# main-stm-02_2.net
KiCad netlist of a schematic drawn in EAGLE
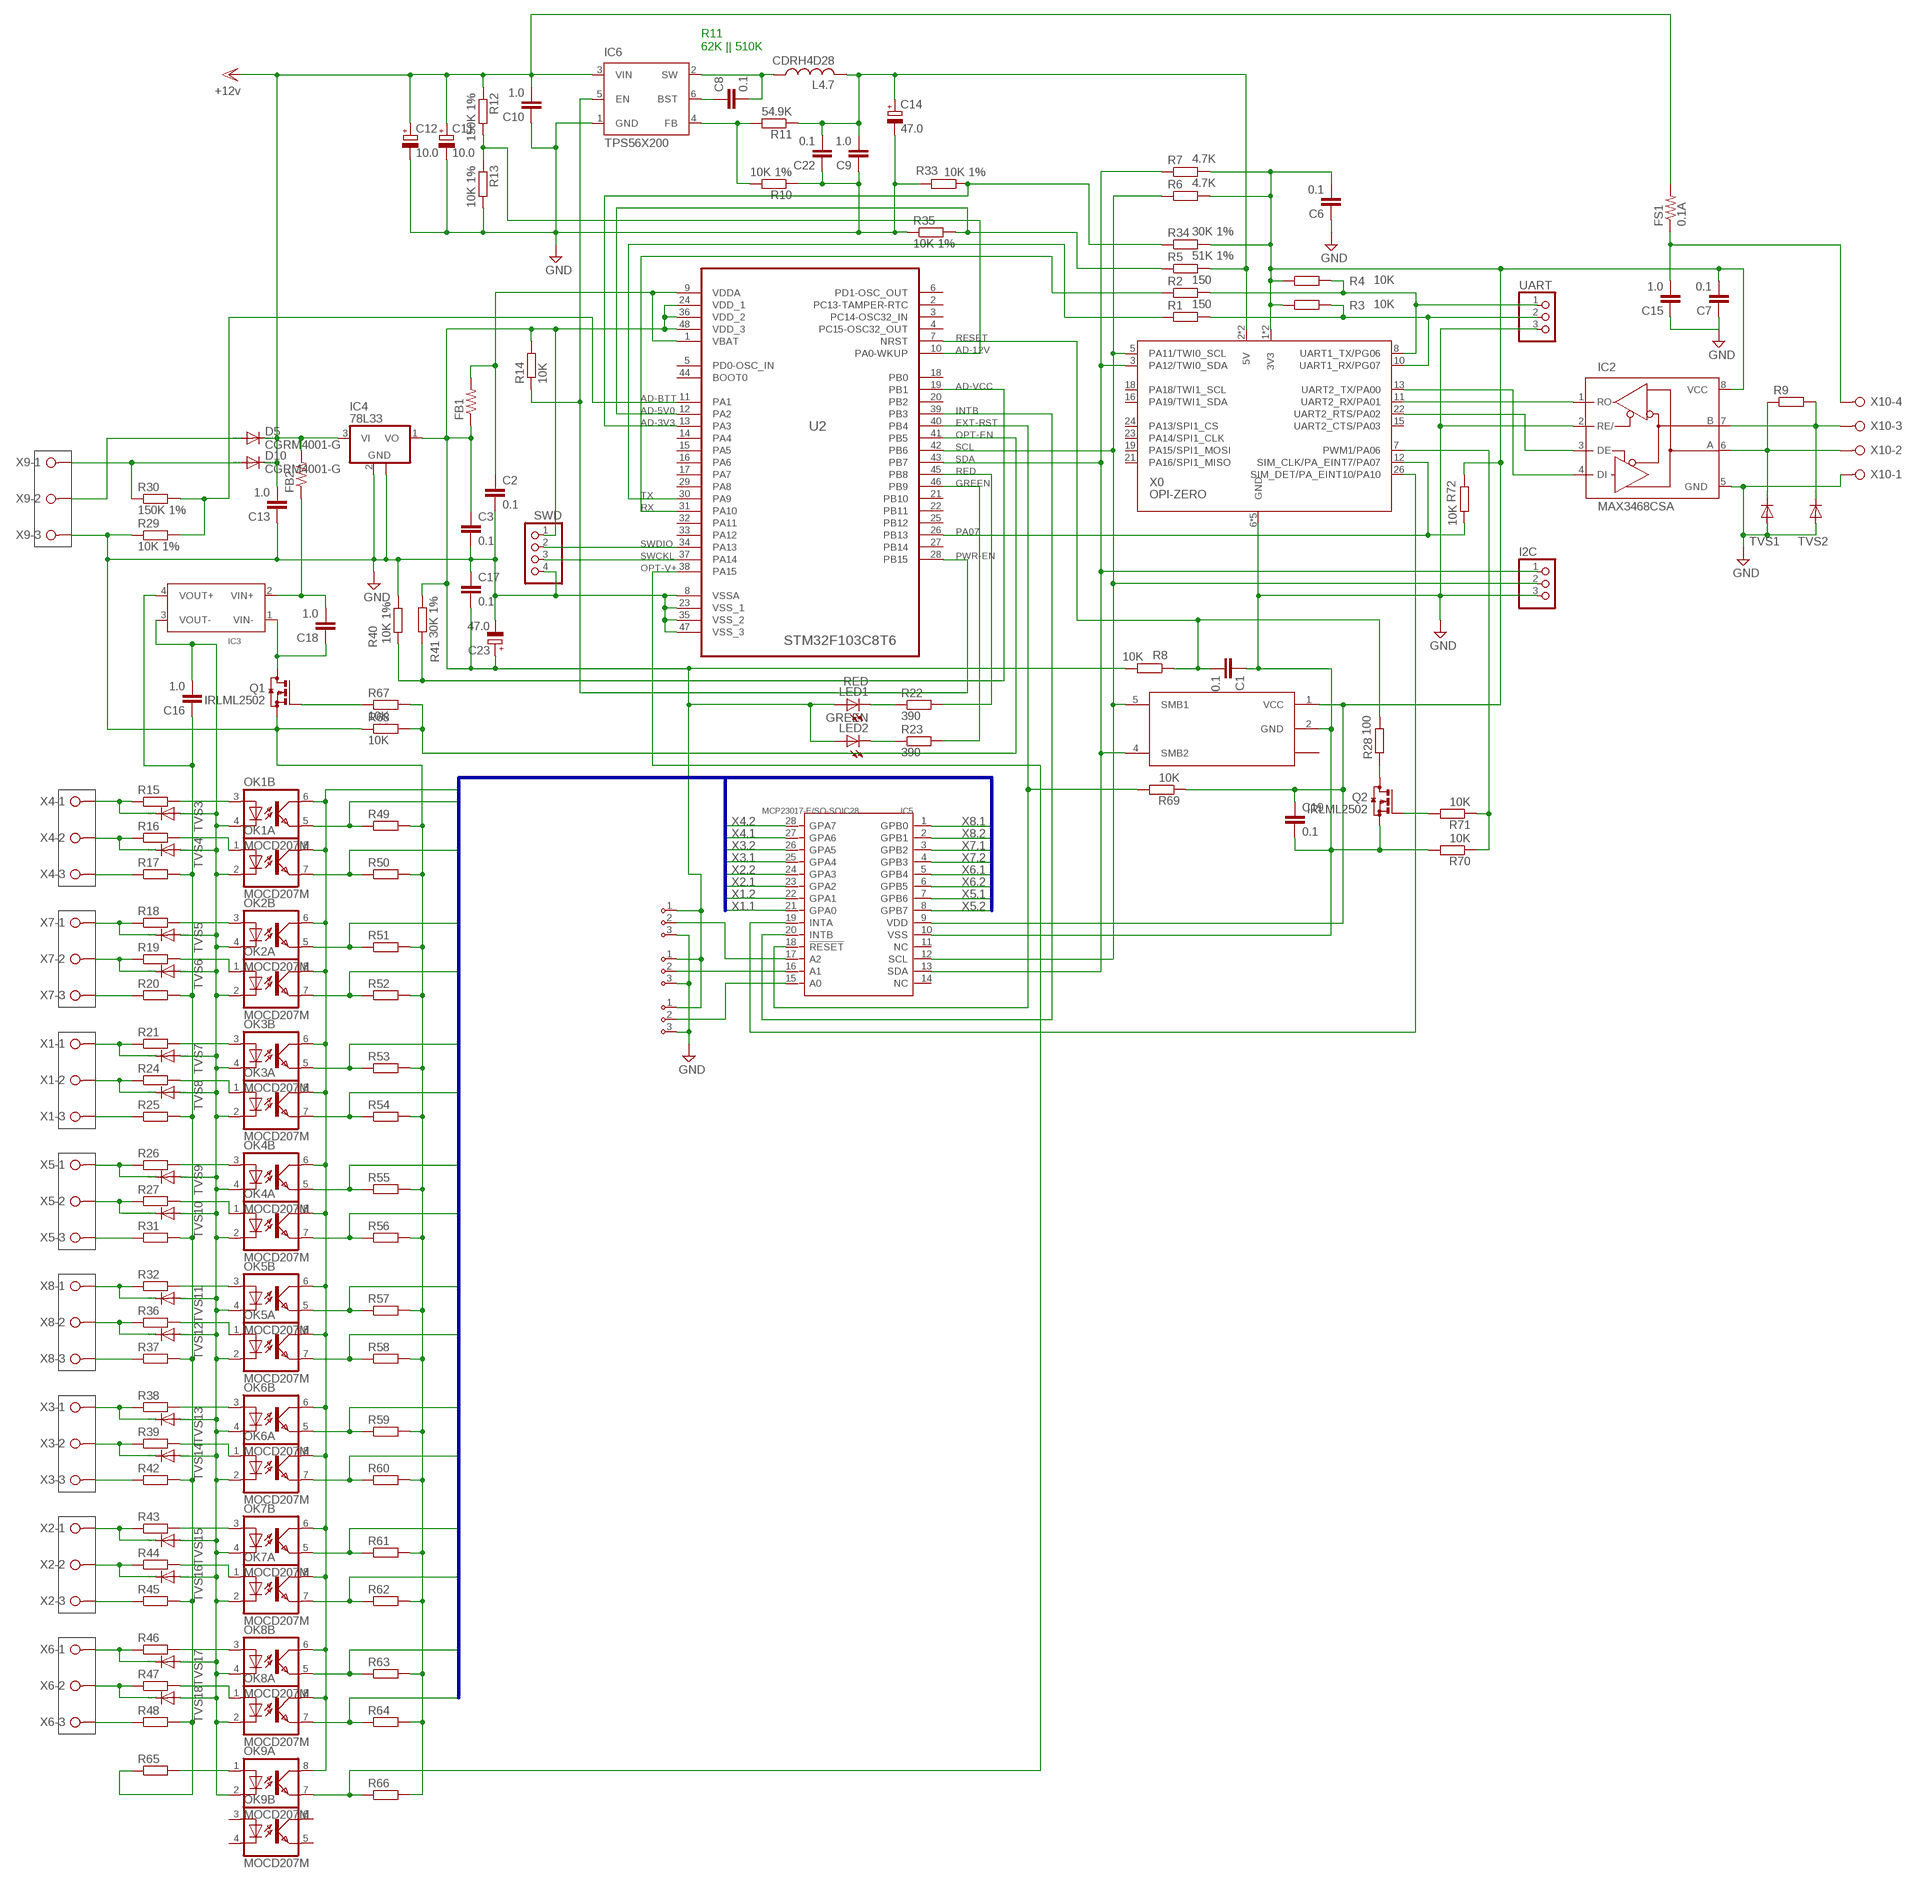
[diagram p0: schematic, sheet 1]

(export (version "E")
  (design (tool "Eeschema 10.0.6"))
  (components
    (comp (ref "A0")
      (value "ADDR3PIN0603")
      (footprint "eagle-import:0603-3PIN")
      (libsource (lib "eagle-import") (part "ADDR3PIN0603"))
    )
    (comp (ref "A1")
      (value "ADDR3PIN0603")
      (footprint "eagle-import:0603-3PIN")
      (libsource (lib "eagle-import") (part "ADDR3PIN0603"))
    )
    (comp (ref "A2")
      (value "ADDR3PIN0603")
      (footprint "eagle-import:0603-3PIN")
      (libsource (lib "eagle-import") (part "ADDR3PIN0603"))
    )
    (comp (ref "C1")
      (value "0.1")
      (footprint "eagle-import:C0603")
      (libsource (lib "eagle-import") (part "C-EUC0603"))
    )
    (comp (ref "C2")
      (value "0.1")
      (footprint "eagle-import:C0603")
      (libsource (lib "eagle-import") (part "C-EUC0603"))
    )
    (comp (ref "C3")
      (value "0.1")
      (footprint "eagle-import:C0603")
      (libsource (lib "eagle-import") (part "C-EUC0603"))
    )
    (comp (ref "C6")
      (value "0.1")
      (footprint "eagle-import:C0805")
      (libsource (lib "eagle-import") (part "C-EUC0805"))
    )
    (comp (ref "C7")
      (value "0.1")
      (footprint "eagle-import:C0805")
      (libsource (lib "eagle-import") (part "C-EUC0805"))
    )
    (comp (ref "C8")
      (value "0.1")
      (footprint "eagle-import:C0805")
      (libsource (lib "eagle-import") (part "C-EUC0805"))
    )
    (comp (ref "C9")
      (value "1.0")
      (footprint "eagle-import:C0805")
      (libsource (lib "eagle-import") (part "C-EUC0805"))
    )
    (comp (ref "C10")
      (value "1.0")
      (footprint "eagle-import:C1206")
      (libsource (lib "eagle-import") (part "C-EUC1206"))
    )
    (comp (ref "C11")
      (value "10.0")
      (footprint "eagle-import:C_6032-28R")
      (libsource (lib "eagle-import") (part "CPOL-EUC/6032-28R"))
    )
    (comp (ref "C12")
      (value "10.0")
      (footprint "eagle-import:C_6032-28R")
      (libsource (lib "eagle-import") (part "CPOL-EUC/6032-28R"))
    )
    (comp (ref "C13")
      (value "1.0")
      (footprint "eagle-import:C1206")
      (libsource (lib "eagle-import") (part "C-EUC1206"))
    )
    (comp (ref "C14")
      (value "47.0")
      (footprint "eagle-import:B_3528-21R")
      (libsource (lib "eagle-import") (part "CPOL-EUB/3528-21R"))
    )
    (comp (ref "C15")
      (value "1.0")
      (footprint "eagle-import:C1206")
      (libsource (lib "eagle-import") (part "C-EUC1206"))
    )
    (comp (ref "C16")
      (value "1.0")
      (footprint "eagle-import:C1206")
      (libsource (lib "eagle-import") (part "C-EUC1206"))
    )
    (comp (ref "C17")
      (value "0.1")
      (footprint "eagle-import:C0603")
      (libsource (lib "eagle-import") (part "C-EUC0603"))
    )
    (comp (ref "C18")
      (value "1.0")
      (footprint "eagle-import:C1206")
      (libsource (lib "eagle-import") (part "C-EUC1206"))
    )
    (comp (ref "C19")
      (value "0.1")
      (footprint "eagle-import:C0603")
      (libsource (lib "eagle-import") (part "C-EUC0603"))
    )
    (comp (ref "C22")
      (value "0.1")
      (footprint "eagle-import:C0805")
      (libsource (lib "eagle-import") (part "C-EUC0805"))
    )
    (comp (ref "C23")
      (value "47.0")
      (footprint "eagle-import:B_3528-21R")
      (libsource (lib "eagle-import") (part "CPOL-EUB/3528-21R"))
    )
    (comp (ref "D5")
      (value "CGRM4001-G")
      (footprint "eagle-import:SOD-123_MINI-SMA")
      (libsource (lib "eagle-import") (part "CGRM400-G1"))
    )
    (comp (ref "D10")
      (value "CGRM4001-G")
      (footprint "eagle-import:SOD-123_MINI-SMA")
      (libsource (lib "eagle-import") (part "CGRM400-G1"))
    )
    (comp (ref "FB1")
      (value "R-US_R0805")
      (footprint "eagle-import:R0805")
      (libsource (lib "eagle-import") (part "R-US_R0805"))
    )
    (comp (ref "FB2")
      (value "R-US_R1206")
      (footprint "eagle-import:R1206")
      (libsource (lib "eagle-import") (part "R-US_R1206"))
    )
    (comp (ref "FS1")
      (value "0.1A")
      (footprint "eagle-import:R1210")
      (libsource (lib "eagle-import") (part "R-US_R1210"))
    )
    (comp (ref "I2C")
      (value "PINHD-1X3")
      (footprint "eagle-import:1X03")
      (libsource (lib "eagle-import") (part "PINHD-1X3"))
    )
    (comp (ref "IC2")
      (value "MAX3468CSA")
      (footprint "eagle-import:SO08")
      (fields (field (name "MPN") "MAX3468CSA+"))
      (libsource (lib "eagle-import") (part "MAX34SA68C"))
    )
    (comp (ref "IC3")
      (value "DC-DC-CONV-4PIN-ISOLATINGMURATA-NME-05-12-SERIES")
      (footprint "eagle-import:DC-DC-MURATA-NME-05-12-SERIES")
      (libsource (lib "eagle-import") (part "DC-DC-CONV-4PIN-ISOLATINGMURATA-NME-05-12-SERIES"))
    )
    (comp (ref "IC4")
      (value "78L33")
      (footprint "eagle-import:SOT89")
      (libsource (lib "eagle-import") (part "78LF05"))
    )
    (comp (ref "IC5")
      (value "MCP23017-E/SO-SOIC28")
      (footprint "eagle-import:SOIC28-1.27-17.9X7.5MM")
      (fields (field (name "MPN") "MCP23017-E/SO"))
      (libsource (lib "eagle-import") (part "INTERFACE-MCP23017-E(SOIC28)"))
    )
    (comp (ref "IC6")
      (value "TPS56X200")
      (footprint "eagle-import:TSOT23-6_DDC")
      (libsource (lib "eagle-import") (part "TPS56X200"))
    )
    (comp (ref "IC7")
      (value "LTC1694")
      (footprint "eagle-import:SOT23-5")
      (libsource (lib "eagle-import") (part "LTC1694"))
    )
    (comp (ref "L4.7")
      (value "CDRH4D28")
      (footprint "eagle-import:CDRH4D28")
      (libsource (lib "eagle-import") (part "CDRH4D28"))
    )
    (comp (ref "LED1")
      (value "RED")
      (footprint "eagle-import:CHIPLED_1206")
      (libsource (lib "eagle-import") (part "LEDCHIPLED_1206"))
    )
    (comp (ref "LED2")
      (value "GREEN")
      (footprint "eagle-import:CHIPLED_1206")
      (libsource (lib "eagle-import") (part "LEDCHIPLED_1206"))
    )
    (comp (ref "OK1")
      (value "MOCD207M")
      (footprint "eagle-import:SOIC08-FAIRCHILD")
      (fields (field (name "MF") "FAIRCHILD SEMICONDUCTOR") (field (name "MPN") "MOCD207-M"))
      (libsource (lib "eagle-import") (part "MOCD20M7"))
    )
    (comp (ref "OK2")
      (value "MOCD207M")
      (footprint "eagle-import:SOIC08-FAIRCHILD")
      (fields (field (name "MF") "FAIRCHILD SEMICONDUCTOR") (field (name "MPN") "MOCD207-M"))
      (libsource (lib "eagle-import") (part "MOCD20M7"))
    )
    (comp (ref "OK3")
      (value "MOCD207M")
      (footprint "eagle-import:SOIC08-FAIRCHILD")
      (fields (field (name "MF") "FAIRCHILD SEMICONDUCTOR") (field (name "MPN") "MOCD207-M"))
      (libsource (lib "eagle-import") (part "MOCD20M7"))
    )
    (comp (ref "OK4")
      (value "MOCD207M")
      (footprint "eagle-import:SOIC08-FAIRCHILD")
      (fields (field (name "MF") "FAIRCHILD SEMICONDUCTOR") (field (name "MPN") "MOCD207-M"))
      (libsource (lib "eagle-import") (part "MOCD20M7"))
    )
    (comp (ref "OK5")
      (value "MOCD207M")
      (footprint "eagle-import:SOIC08-FAIRCHILD")
      (fields (field (name "MF") "FAIRCHILD SEMICONDUCTOR") (field (name "MPN") "MOCD207-M"))
      (libsource (lib "eagle-import") (part "MOCD20M7"))
    )
    (comp (ref "OK6")
      (value "MOCD207M")
      (footprint "eagle-import:SOIC08-FAIRCHILD")
      (fields (field (name "MF") "FAIRCHILD SEMICONDUCTOR") (field (name "MPN") "MOCD207-M"))
      (libsource (lib "eagle-import") (part "MOCD20M7"))
    )
    (comp (ref "OK7")
      (value "MOCD207M")
      (footprint "eagle-import:SOIC08-FAIRCHILD")
      (fields (field (name "MF") "FAIRCHILD SEMICONDUCTOR") (field (name "MPN") "MOCD207-M"))
      (libsource (lib "eagle-import") (part "MOCD20M7"))
    )
    (comp (ref "OK8")
      (value "MOCD207M")
      (footprint "eagle-import:SOIC08-FAIRCHILD")
      (fields (field (name "MF") "FAIRCHILD SEMICONDUCTOR") (field (name "MPN") "MOCD207-M"))
      (libsource (lib "eagle-import") (part "MOCD20M7"))
    )
    (comp (ref "OK9")
      (value "MOCD207M")
      (footprint "eagle-import:SOIC08-FAIRCHILD")
      (fields (field (name "MF") "FAIRCHILD SEMICONDUCTOR") (field (name "MPN") "MOCD207-M"))
      (libsource (lib "eagle-import") (part "MOCD20M7"))
    )
    (comp (ref "Q1")
      (value "IRLML2502")
      (footprint "eagle-import:SOT23")
      (libsource (lib "eagle-import") (part "IRLML2502"))
    )
    (comp (ref "Q2")
      (value "IRLML2502")
      (footprint "eagle-import:SOT23")
      (libsource (lib "eagle-import") (part "IRLML2502"))
    )
    (comp (ref "R1")
      (value "150")
      (footprint "eagle-import:R0603")
      (libsource (lib "eagle-import") (part "R-EU_R0603"))
    )
    (comp (ref "R2")
      (value "150")
      (footprint "eagle-import:R0603")
      (libsource (lib "eagle-import") (part "R-EU_R0603"))
    )
    (comp (ref "R3")
      (value "10K")
      (footprint "eagle-import:R0603")
      (libsource (lib "eagle-import") (part "R-EU_R0603"))
    )
    (comp (ref "R4")
      (value "10K")
      (footprint "eagle-import:R0603")
      (libsource (lib "eagle-import") (part "R-EU_R0603"))
    )
    (comp (ref "R5")
      (value "51K 1%")
      (footprint "eagle-import:R0603")
      (libsource (lib "eagle-import") (part "R-EU_R0603"))
    )
    (comp (ref "R6")
      (value "4.7K")
      (footprint "eagle-import:R0603")
      (libsource (lib "eagle-import") (part "R-EU_R0603"))
    )
    (comp (ref "R7")
      (value "4.7K")
      (footprint "eagle-import:R0603")
      (libsource (lib "eagle-import") (part "R-EU_R0603"))
    )
    (comp (ref "R8")
      (value "10K")
      (footprint "eagle-import:R0603")
      (libsource (lib "eagle-import") (part "R-EU_R0603"))
    )
    (comp (ref "R9")
      (value "R-EU_R1206")
      (footprint "eagle-import:R1206")
      (libsource (lib "eagle-import") (part "R-EU_R1206"))
    )
    (comp (ref "R10")
      (value "10K 1%")
      (footprint "eagle-import:R0603")
      (libsource (lib "eagle-import") (part "R-EU_R0603"))
    )
    (comp (ref "R11")
      (value "54.9K")
      (footprint "eagle-import:R0603")
      (libsource (lib "eagle-import") (part "R-EU_R0603"))
    )
    (comp (ref "R12")
      (value "150K 1%")
      (footprint "eagle-import:R0603")
      (libsource (lib "eagle-import") (part "R-EU_R0603"))
    )
    (comp (ref "R13")
      (value "10K 1%")
      (footprint "eagle-import:R0603")
      (libsource (lib "eagle-import") (part "R-EU_R0603"))
    )
    (comp (ref "R14")
      (value "10K")
      (footprint "eagle-import:R0603")
      (libsource (lib "eagle-import") (part "R-EU_R0603"))
    )
    (comp (ref "R15")
      (value "R-EU_R0603")
      (footprint "eagle-import:R0603")
      (libsource (lib "eagle-import") (part "R-EU_R0603"))
    )
    (comp (ref "R16")
      (value "R-EU_R0603")
      (footprint "eagle-import:R0603")
      (libsource (lib "eagle-import") (part "R-EU_R0603"))
    )
    (comp (ref "R17")
      (value "R-EU_R0603")
      (footprint "eagle-import:R0603")
      (libsource (lib "eagle-import") (part "R-EU_R0603"))
    )
    (comp (ref "R18")
      (value "R-EU_R0603")
      (footprint "eagle-import:R0603")
      (libsource (lib "eagle-import") (part "R-EU_R0603"))
    )
    (comp (ref "R19")
      (value "R-EU_R0603")
      (footprint "eagle-import:R0603")
      (libsource (lib "eagle-import") (part "R-EU_R0603"))
    )
    (comp (ref "R20")
      (value "R-EU_R0603")
      (footprint "eagle-import:R0603")
      (libsource (lib "eagle-import") (part "R-EU_R0603"))
    )
    (comp (ref "R21")
      (value "R-EU_R0603")
      (footprint "eagle-import:R0603")
      (libsource (lib "eagle-import") (part "R-EU_R0603"))
    )
    (comp (ref "R22")
      (value "390")
      (footprint "eagle-import:R0603")
      (libsource (lib "eagle-import") (part "R-EU_R0603"))
    )
    (comp (ref "R23")
      (value "390")
      (footprint "eagle-import:R0603")
      (libsource (lib "eagle-import") (part "R-EU_R0603"))
    )
    (comp (ref "R24")
      (value "R-EU_R0603")
      (footprint "eagle-import:R0603")
      (libsource (lib "eagle-import") (part "R-EU_R0603"))
    )
    (comp (ref "R25")
      (value "R-EU_R0603")
      (footprint "eagle-import:R0603")
      (libsource (lib "eagle-import") (part "R-EU_R0603"))
    )
    (comp (ref "R26")
      (value "R-EU_R0603")
      (footprint "eagle-import:R0603")
      (libsource (lib "eagle-import") (part "R-EU_R0603"))
    )
    (comp (ref "R27")
      (value "R-EU_R0603")
      (footprint "eagle-import:R0603")
      (libsource (lib "eagle-import") (part "R-EU_R0603"))
    )
    (comp (ref "R28")
      (value "100")
      (footprint "eagle-import:R0603")
      (libsource (lib "eagle-import") (part "R-EU_R0603"))
    )
    (comp (ref "R29")
      (value "10K 1%")
      (footprint "eagle-import:R0603")
      (libsource (lib "eagle-import") (part "R-EU_R0603"))
    )
    (comp (ref "R30")
      (value "150K 1%")
      (footprint "eagle-import:R0603")
      (libsource (lib "eagle-import") (part "R-EU_R0603"))
    )
    (comp (ref "R31")
      (value "R-EU_R0603")
      (footprint "eagle-import:R0603")
      (libsource (lib "eagle-import") (part "R-EU_R0603"))
    )
    (comp (ref "R32")
      (value "R-EU_R0603")
      (footprint "eagle-import:R0603")
      (libsource (lib "eagle-import") (part "R-EU_R0603"))
    )
    (comp (ref "R33")
      (value "10K 1%")
      (footprint "eagle-import:R0603")
      (libsource (lib "eagle-import") (part "R-EU_R0603"))
    )
    (comp (ref "R34")
      (value "30K 1%")
      (footprint "eagle-import:R0603")
      (libsource (lib "eagle-import") (part "R-EU_R0603"))
    )
    (comp (ref "R35")
      (value "10K 1%")
      (footprint "eagle-import:R0603")
      (libsource (lib "eagle-import") (part "R-EU_R0603"))
    )
    (comp (ref "R36")
      (value "R-EU_R0603")
      (footprint "eagle-import:R0603")
      (libsource (lib "eagle-import") (part "R-EU_R0603"))
    )
    (comp (ref "R37")
      (value "R-EU_R0603")
      (footprint "eagle-import:R0603")
      (libsource (lib "eagle-import") (part "R-EU_R0603"))
    )
    (comp (ref "R38")
      (value "R-EU_R0603")
      (footprint "eagle-import:R0603")
      (libsource (lib "eagle-import") (part "R-EU_R0603"))
    )
    (comp (ref "R39")
      (value "R-EU_R0603")
      (footprint "eagle-import:R0603")
      (libsource (lib "eagle-import") (part "R-EU_R0603"))
    )
    (comp (ref "R40")
      (value "10K 1%")
      (footprint "eagle-import:R0603")
      (libsource (lib "eagle-import") (part "R-EU_R0603"))
    )
    (comp (ref "R41")
      (value "30K 1%")
      (footprint "eagle-import:R0603")
      (libsource (lib "eagle-import") (part "R-EU_R0603"))
    )
    (comp (ref "R42")
      (value "R-EU_R0603")
      (footprint "eagle-import:R0603")
      (libsource (lib "eagle-import") (part "R-EU_R0603"))
    )
    (comp (ref "R43")
      (value "R-EU_R0603")
      (footprint "eagle-import:R0603")
      (libsource (lib "eagle-import") (part "R-EU_R0603"))
    )
    (comp (ref "R44")
      (value "R-EU_R0603")
      (footprint "eagle-import:R0603")
      (libsource (lib "eagle-import") (part "R-EU_R0603"))
    )
    (comp (ref "R45")
      (value "R-EU_R0603")
      (footprint "eagle-import:R0603")
      (libsource (lib "eagle-import") (part "R-EU_R0603"))
    )
    (comp (ref "R46")
      (value "R-EU_R0603")
      (footprint "eagle-import:R0603")
      (libsource (lib "eagle-import") (part "R-EU_R0603"))
    )
    (comp (ref "R47")
      (value "R-EU_R0603")
      (footprint "eagle-import:R0603")
      (libsource (lib "eagle-import") (part "R-EU_R0603"))
    )
    (comp (ref "R48")
      (value "R-EU_R0603")
      (footprint "eagle-import:R0603")
      (libsource (lib "eagle-import") (part "R-EU_R0603"))
    )
    (comp (ref "R49")
      (value "R-EU_R0603")
      (footprint "eagle-import:R0603")
      (libsource (lib "eagle-import") (part "R-EU_R0603"))
    )
    (comp (ref "R50")
      (value "R-EU_R0603")
      (footprint "eagle-import:R0603")
      (libsource (lib "eagle-import") (part "R-EU_R0603"))
    )
    (comp (ref "R51")
      (value "R-EU_R0603")
      (footprint "eagle-import:R0603")
      (libsource (lib "eagle-import") (part "R-EU_R0603"))
    )
    (comp (ref "R52")
      (value "R-EU_R0603")
      (footprint "eagle-import:R0603")
      (libsource (lib "eagle-import") (part "R-EU_R0603"))
    )
    (comp (ref "R53")
      (value "R-EU_R0603")
      (footprint "eagle-import:R0603")
      (libsource (lib "eagle-import") (part "R-EU_R0603"))
    )
    (comp (ref "R54")
      (value "R-EU_R0603")
      (footprint "eagle-import:R0603")
      (libsource (lib "eagle-import") (part "R-EU_R0603"))
    )
    (comp (ref "R55")
      (value "R-EU_R0603")
      (footprint "eagle-import:R0603")
      (libsource (lib "eagle-import") (part "R-EU_R0603"))
    )
    (comp (ref "R56")
      (value "R-EU_R0603")
      (footprint "eagle-import:R0603")
      (libsource (lib "eagle-import") (part "R-EU_R0603"))
    )
    (comp (ref "R57")
      (value "R-EU_R0603")
      (footprint "eagle-import:R0603")
      (libsource (lib "eagle-import") (part "R-EU_R0603"))
    )
    (comp (ref "R58")
      (value "R-EU_R0603")
      (footprint "eagle-import:R0603")
      (libsource (lib "eagle-import") (part "R-EU_R0603"))
    )
    (comp (ref "R59")
      (value "R-EU_R0603")
      (footprint "eagle-import:R0603")
      (libsource (lib "eagle-import") (part "R-EU_R0603"))
    )
    (comp (ref "R60")
      (value "R-EU_R0603")
      (footprint "eagle-import:R0603")
      (libsource (lib "eagle-import") (part "R-EU_R0603"))
    )
    (comp (ref "R61")
      (value "R-EU_R0603")
      (footprint "eagle-import:R0603")
      (libsource (lib "eagle-import") (part "R-EU_R0603"))
    )
    (comp (ref "R62")
      (value "R-EU_R0603")
      (footprint "eagle-import:R0603")
      (libsource (lib "eagle-import") (part "R-EU_R0603"))
    )
    (comp (ref "R63")
      (value "R-EU_R0603")
      (footprint "eagle-import:R0603")
      (libsource (lib "eagle-import") (part "R-EU_R0603"))
    )
    (comp (ref "R64")
      (value "R-EU_R0603")
      (footprint "eagle-import:R0603")
      (libsource (lib "eagle-import") (part "R-EU_R0603"))
    )
    (comp (ref "R65")
      (value "R-EU_R0603")
      (footprint "eagle-import:R0603")
      (libsource (lib "eagle-import") (part "R-EU_R0603"))
    )
    (comp (ref "R66")
      (value "R-EU_R0603")
      (footprint "eagle-import:R0603")
      (libsource (lib "eagle-import") (part "R-EU_R0603"))
    )
    (comp (ref "R67")
      (value "10K")
      (footprint "eagle-import:R0603")
      (libsource (lib "eagle-import") (part "R-EU_R0603"))
    )
    (comp (ref "R68")
      (value "10K")
      (footprint "eagle-import:R0603")
      (libsource (lib "eagle-import") (part "R-EU_R0603"))
    )
    (comp (ref "R69")
      (value "10K")
      (footprint "eagle-import:R0603")
      (libsource (lib "eagle-import") (part "R-EU_R0603"))
    )
    (comp (ref "R70")
      (value "10K")
      (footprint "eagle-import:R0603")
      (libsource (lib "eagle-import") (part "R-EU_R0603"))
    )
    (comp (ref "R71")
      (value "10K")
      (footprint "eagle-import:R0603")
      (libsource (lib "eagle-import") (part "R-EU_R0603"))
    )
    (comp (ref "R72")
      (value "10K")
      (footprint "eagle-import:R0603")
      (libsource (lib "eagle-import") (part "R-EU_R0603"))
    )
    (comp (ref "SWD")
      (value "PINHD-1X4")
      (footprint "eagle-import:1X04")
      (libsource (lib "eagle-import") (part "PINHD-1X4"))
    )
    (comp (ref "TVS1")
      (value "DIODE-SOD323-W")
      (footprint "eagle-import:SOD323-W")
      (libsource (lib "eagle-import") (part "DIODE-SOD323-W"))
    )
    (comp (ref "TVS2")
      (value "DIODE-SOD323-W")
      (footprint "eagle-import:SOD323-W")
      (libsource (lib "eagle-import") (part "DIODE-SOD323-W"))
    )
    (comp (ref "TVS3")
      (value "DIODE-SOD323-W")
      (footprint "eagle-import:SOD323-W")
      (libsource (lib "eagle-import") (part "DIODE-SOD323-W"))
    )
    (comp (ref "TVS4")
      (value "DIODE-SOD323-W")
      (footprint "eagle-import:SOD323-W")
      (libsource (lib "eagle-import") (part "DIODE-SOD323-W"))
    )
    (comp (ref "TVS5")
      (value "DIODE-SOD323-W")
      (footprint "eagle-import:SOD323-W")
      (libsource (lib "eagle-import") (part "DIODE-SOD323-W"))
    )
    (comp (ref "TVS6")
      (value "DIODE-SOD323-W")
      (footprint "eagle-import:SOD323-W")
      (libsource (lib "eagle-import") (part "DIODE-SOD323-W"))
    )
    (comp (ref "TVS7")
      (value "DIODE-SOD323-W")
      (footprint "eagle-import:SOD323-W")
      (libsource (lib "eagle-import") (part "DIODE-SOD323-W"))
    )
    (comp (ref "TVS8")
      (value "DIODE-SOD323-W")
      (footprint "eagle-import:SOD323-W")
      (libsource (lib "eagle-import") (part "DIODE-SOD323-W"))
    )
    (comp (ref "TVS9")
      (value "DIODE-SOD323-W")
      (footprint "eagle-import:SOD323-W")
      (libsource (lib "eagle-import") (part "DIODE-SOD323-W"))
    )
    (comp (ref "TVS10")
      (value "DIODE-SOD323-W")
      (footprint "eagle-import:SOD323-W")
      (libsource (lib "eagle-import") (part "DIODE-SOD323-W"))
    )
    (comp (ref "TVS11")
      (value "DIODE-SOD323-W")
      (footprint "eagle-import:SOD323-W")
      (libsource (lib "eagle-import") (part "DIODE-SOD323-W"))
    )
    (comp (ref "TVS12")
      (value "DIODE-SOD323-W")
      (footprint "eagle-import:SOD323-W")
      (libsource (lib "eagle-import") (part "DIODE-SOD323-W"))
    )
    (comp (ref "TVS13")
      (value "DIODE-SOD323-W")
      (footprint "eagle-import:SOD323-W")
      (libsource (lib "eagle-import") (part "DIODE-SOD323-W"))
    )
    (comp (ref "TVS14")
      (value "DIODE-SOD323-W")
      (footprint "eagle-import:SOD323-W")
      (libsource (lib "eagle-import") (part "DIODE-SOD323-W"))
    )
    (comp (ref "TVS15")
      (value "DIODE-SOD323-W")
      (footprint "eagle-import:SOD323-W")
      (libsource (lib "eagle-import") (part "DIODE-SOD323-W"))
    )
    (comp (ref "TVS16")
      (value "DIODE-SOD323-W")
      (footprint "eagle-import:SOD323-W")
      (libsource (lib "eagle-import") (part "DIODE-SOD323-W"))
    )
    (comp (ref "TVS17")
      (value "DIODE-SOD323-W")
      (footprint "eagle-import:SOD323-W")
      (libsource (lib "eagle-import") (part "DIODE-SOD323-W"))
    )
    (comp (ref "TVS18")
      (value "DIODE-SOD323-W")
      (footprint "eagle-import:SOD323-W")
      (libsource (lib "eagle-import") (part "DIODE-SOD323-W"))
    )
    (comp (ref "U2")
      (value "STM32F103C8T6")
      (footprint "eagle-import:QFP50P900X900X160-48N")
      (fields (field (name "MPN") "STM32F100CBT6B"))
      (libsource (lib "eagle-import") (part "STM32F100CBT6B"))
    )
    (comp (ref "UART")
      (value "PINHD-1X3")
      (footprint "eagle-import:1X03")
      (libsource (lib "eagle-import") (part "PINHD-1X3"))
    )
    (comp (ref "X0")
      (value "OPI-ZERO")
      (footprint "eagle-import:OPI0")
      (libsource (lib "eagle-import") (part "OPI-ZERO"))
    )
    (comp (ref "X1")
      (value "W237-03P")
      (footprint "eagle-import:W237-133")
      (libsource (lib "eagle-import") (part "W237-03P"))
    )
    (comp (ref "X2")
      (value "W237-03P")
      (footprint "eagle-import:W237-133")
      (libsource (lib "eagle-import") (part "W237-03P"))
    )
    (comp (ref "X3")
      (value "W237-03P")
      (footprint "eagle-import:W237-133")
      (libsource (lib "eagle-import") (part "W237-03P"))
    )
    (comp (ref "X4")
      (value "W237-03P")
      (footprint "eagle-import:W237-133")
      (libsource (lib "eagle-import") (part "W237-03P"))
    )
    (comp (ref "X5")
      (value "W237-03P")
      (footprint "eagle-import:W237-133")
      (libsource (lib "eagle-import") (part "W237-03P"))
    )
    (comp (ref "X6")
      (value "W237-03P")
      (footprint "eagle-import:W237-133")
      (libsource (lib "eagle-import") (part "W237-03P"))
    )
    (comp (ref "X7")
      (value "W237-03P")
      (footprint "eagle-import:W237-133")
      (libsource (lib "eagle-import") (part "W237-03P"))
    )
    (comp (ref "X8")
      (value "W237-03P")
      (footprint "eagle-import:W237-133")
      (libsource (lib "eagle-import") (part "W237-03P"))
    )
    (comp (ref "X9")
      (value "W237-03P")
      (footprint "eagle-import:W237-133")
      (libsource (lib "eagle-import") (part "W237-03P"))
    )
    (comp (ref "X10")
      (value "W237-04P")
      (footprint "eagle-import:W237-4P")
      (libsource (lib "eagle-import") (part "W237-04P"))
    )
  )
  (nets
    (net (code "1") (name "+12v") (class "Default")
      (node (ref "C10") (pin "2") (pinfunction "2_2") (pintype "passive"))
      (node (ref "C11") (pin "+") (pinfunction "+_+") (pintype "passive"))
      (node (ref "C12") (pin "+") (pinfunction "+_+") (pintype "passive"))
      (node (ref "C13") (pin "2") (pinfunction "2_2") (pintype "passive"))
      (node (ref "D10") (pin "C") (pinfunction "C_C") (pintype "passive"))
      (node (ref "D5") (pin "C") (pinfunction "C_C") (pintype "passive"))
      (node (ref "FB2") (pin "2") (pinfunction "2_2") (pintype "passive"))
      (node (ref "FS1") (pin "2") (pinfunction "2_2") (pintype "passive"))
      (node (ref "IC4") (pin "3") (pinfunction "VI_3") (pintype "input"))
      (node (ref "IC6") (pin "3") (pinfunction "VIN_3") (pintype "input"))
      (node (ref "R12") (pin "1") (pinfunction "1_1") (pintype "passive"))
    )
    (net (code "2") (name "/AD-3V3") (class "Default")
      (node (ref "R33") (pin "1") (pinfunction "1_1") (pintype "passive"))
      (node (ref "R34") (pin "1") (pinfunction "1_1") (pintype "passive"))
      (node (ref "U2") (pin "13") (pinfunction "PA3_13") (pintype "bidirectional"))
    )
    (net (code "3") (name "/AD-5V0") (class "Default")
      (node (ref "R35") (pin "2") (pinfunction "2_2") (pintype "passive"))
      (node (ref "R5") (pin "1") (pinfunction "1_1") (pintype "passive"))
      (node (ref "U2") (pin "12") (pinfunction "PA2_12") (pintype "bidirectional"))
    )
    (net (code "4") (name "/AD-12V") (class "Default")
      (node (ref "R12") (pin "2") (pinfunction "2_2") (pintype "passive"))
      (node (ref "R13") (pin "1") (pinfunction "1_1") (pintype "passive"))
      (node (ref "U2") (pin "10") (pinfunction "PA0-WKUP_10") (pintype "bidirectional"))
    )
    (net (code "5") (name "/AD-BTT") (class "Default")
      (node (ref "R29") (pin "2") (pinfunction "2_2") (pintype "passive"))
      (node (ref "R30") (pin "2") (pinfunction "2_2") (pintype "passive"))
      (node (ref "U2") (pin "11") (pinfunction "PA1_11") (pintype "bidirectional"))
    )
    (net (code "6") (name "/AD-VCC") (class "Default")
      (node (ref "R40") (pin "2") (pinfunction "2_2") (pintype "passive"))
      (node (ref "R41") (pin "1") (pinfunction "1_1") (pintype "passive"))
      (node (ref "U2") (pin "19") (pinfunction "PB1_19") (pintype "bidirectional"))
    )
    (net (code "7") (name "/EXT-RST") (class "Default")
      (node (ref "IC5") (pin "18") (pinfunction "~{RESET}_18") (pintype "bidirectional"))
      (node (ref "R69") (pin "2") (pinfunction "2_2") (pintype "passive"))
      (node (ref "U2") (pin "40") (pinfunction "PB4_40") (pintype "bidirectional"))
    )
    (net (code "8") (name "/GREEN") (class "Default")
      (node (ref "R23") (pin "2") (pinfunction "2_2") (pintype "passive"))
      (node (ref "U2") (pin "46") (pinfunction "PB9_46") (pintype "bidirectional"))
    )
    (net (code "9") (name "/INTB") (class "Default")
      (node (ref "IC5") (pin "20") (pinfunction "INTB_20") (pintype "bidirectional"))
      (node (ref "U2") (pin "39") (pinfunction "PB3_39") (pintype "bidirectional"))
    )
    (net (code "10") (name "/OPT-EN") (class "Default")
      (node (ref "R67") (pin "2") (pinfunction "2_2") (pintype "passive"))
      (node (ref "R68") (pin "2") (pinfunction "2_2") (pintype "passive"))
      (node (ref "U2") (pin "41") (pinfunction "PB5_41") (pintype "bidirectional"))
    )
    (net (code "11") (name "/OPT-V+") (class "Default")
      (node (ref "OK9") (pin "7") (pinfunction "EMIT_7") (pintype "passive"))
      (node (ref "R66") (pin "1") (pinfunction "1_1") (pintype "passive"))
      (node (ref "U2") (pin "38") (pinfunction "PA15_38") (pintype "bidirectional"))
    )
    (net (code "12") (name "/PA07") (class "Default")
      (node (ref "R72") (pin "2") (pinfunction "2_2") (pintype "passive"))
      (node (ref "U2") (pin "26") (pinfunction "PB13_26") (pintype "bidirectional"))
      (node (ref "X0") (pin "12") (pinfunction "SIM_CLK/PA_EINT7/PA07_12") (pintype "bidirectional"))
    )
    (net (code "13") (name "/PWR-EN") (class "Default")
      (node (ref "IC6") (pin "5") (pinfunction "EN_5") (pintype "input"))
      (node (ref "R14") (pin "1") (pinfunction "1_1") (pintype "passive"))
      (node (ref "U2") (pin "28") (pinfunction "PB15_28") (pintype "bidirectional"))
    )
    (net (code "14") (name "/RED") (class "Default")
      (node (ref "R22") (pin "2") (pinfunction "2_2") (pintype "passive"))
      (node (ref "U2") (pin "45") (pinfunction "PB8_45") (pintype "bidirectional"))
    )
    (net (code "15") (name "/RESET") (class "Default")
      (node (ref "C1") (pin "2") (pinfunction "2_2") (pintype "passive"))
      (node (ref "R28") (pin "2") (pinfunction "2_2") (pintype "passive"))
      (node (ref "R8") (pin "1") (pinfunction "1_1") (pintype "passive"))
      (node (ref "U2") (pin "7") (pinfunction "NRST_7") (pintype "bidirectional"))
    )
    (net (code "16") (name "/RX") (class "Default")
      (node (ref "R2") (pin "1") (pinfunction "1_1") (pintype "passive"))
      (node (ref "U2") (pin "31") (pinfunction "PA10_31") (pintype "bidirectional"))
    )
    (net (code "17") (name "/SCL") (class "Default")
      (node (ref "I2C") (pin "2") (pinfunction "2_2") (pintype "passive"))
      (node (ref "IC5") (pin "12") (pinfunction "SCL_12") (pintype "bidirectional"))
      (node (ref "IC7") (pin "5") (pinfunction "SMB1_5") (pintype "bidirectional"))
      (node (ref "R6") (pin "1") (pinfunction "1_1") (pintype "passive"))
      (node (ref "U2") (pin "42") (pinfunction "PB6_42") (pintype "bidirectional"))
      (node (ref "X0") (pin "5") (pinfunction "PA11/TWI0_SCL_5") (pintype "bidirectional"))
    )
    (net (code "18") (name "/SDA") (class "Default")
      (node (ref "I2C") (pin "1") (pinfunction "1_1") (pintype "passive"))
      (node (ref "IC5") (pin "13") (pinfunction "SDA_13") (pintype "bidirectional"))
      (node (ref "IC7") (pin "4") (pinfunction "SMB2_4") (pintype "bidirectional"))
      (node (ref "R7") (pin "1") (pinfunction "1_1") (pintype "passive"))
      (node (ref "U2") (pin "43") (pinfunction "PB7_43") (pintype "bidirectional"))
      (node (ref "X0") (pin "3") (pinfunction "PA12/TWI0_SDA_3") (pintype "bidirectional"))
    )
    (net (code "19") (name "/SWCKL") (class "Default")
      (node (ref "SWD") (pin "3") (pinfunction "3_3") (pintype "passive"))
      (node (ref "U2") (pin "37") (pinfunction "PA14_37") (pintype "bidirectional"))
    )
    (net (code "20") (name "/SWDIO") (class "Default")
      (node (ref "SWD") (pin "2") (pinfunction "2_2") (pintype "passive"))
      (node (ref "U2") (pin "34") (pinfunction "PA13_34") (pintype "bidirectional"))
    )
    (net (code "21") (name "/TX") (class "Default")
      (node (ref "R1") (pin "1") (pinfunction "1_1") (pintype "passive"))
      (node (ref "U2") (pin "30") (pinfunction "PA9_30") (pintype "bidirectional"))
    )
    (net (code "22") (name "/X1.1") (class "Default")
      (node (ref "IC5") (pin "21") (pinfunction "GPA0_21") (pintype "bidirectional"))
      (node (ref "OK3") (pin "5") (pinfunction "EMIT_5") (pintype "passive"))
      (node (ref "R53") (pin "1") (pinfunction "1_1") (pintype "passive"))
    )
    (net (code "23") (name "/X1.2") (class "Default")
      (node (ref "IC5") (pin "22") (pinfunction "GPA1_22") (pintype "bidirectional"))
      (node (ref "OK3") (pin "7") (pinfunction "EMIT_7") (pintype "passive"))
      (node (ref "R54") (pin "1") (pinfunction "1_1") (pintype "passive"))
    )
    (net (code "24") (name "/X2.1") (class "Default")
      (node (ref "IC5") (pin "23") (pinfunction "GPA2_23") (pintype "bidirectional"))
      (node (ref "OK7") (pin "5") (pinfunction "EMIT_5") (pintype "passive"))
      (node (ref "R61") (pin "1") (pinfunction "1_1") (pintype "passive"))
    )
    (net (code "25") (name "/X2.2") (class "Default")
      (node (ref "IC5") (pin "24") (pinfunction "GPA3_24") (pintype "bidirectional"))
      (node (ref "OK7") (pin "7") (pinfunction "EMIT_7") (pintype "passive"))
      (node (ref "R62") (pin "1") (pinfunction "1_1") (pintype "passive"))
    )
    (net (code "26") (name "/X3.1") (class "Default")
      (node (ref "IC5") (pin "25") (pinfunction "GPA4_25") (pintype "bidirectional"))
      (node (ref "OK6") (pin "5") (pinfunction "EMIT_5") (pintype "passive"))
      (node (ref "R59") (pin "1") (pinfunction "1_1") (pintype "passive"))
    )
    (net (code "27") (name "/X3.2") (class "Default")
      (node (ref "IC5") (pin "26") (pinfunction "GPA5_26") (pintype "bidirectional"))
      (node (ref "OK6") (pin "7") (pinfunction "EMIT_7") (pintype "passive"))
      (node (ref "R60") (pin "1") (pinfunction "1_1") (pintype "passive"))
    )
    (net (code "28") (name "/X4.1") (class "Default")
      (node (ref "IC5") (pin "27") (pinfunction "GPA6_27") (pintype "bidirectional"))
      (node (ref "OK1") (pin "5") (pinfunction "EMIT_5") (pintype "passive"))
      (node (ref "R49") (pin "1") (pinfunction "1_1") (pintype "passive"))
    )
    (net (code "29") (name "/X4.2") (class "Default")
      (node (ref "IC5") (pin "28") (pinfunction "GPA7_28") (pintype "bidirectional"))
      (node (ref "OK1") (pin "7") (pinfunction "EMIT_7") (pintype "passive"))
      (node (ref "R50") (pin "1") (pinfunction "1_1") (pintype "passive"))
    )
    (net (code "30") (name "/X5.1") (class "Default")
      (node (ref "IC5") (pin "7") (pinfunction "GPB6_7") (pintype "bidirectional"))
      (node (ref "OK4") (pin "5") (pinfunction "EMIT_5") (pintype "passive"))
      (node (ref "R55") (pin "1") (pinfunction "1_1") (pintype "passive"))
    )
    (net (code "31") (name "/X5.2") (class "Default")
      (node (ref "IC5") (pin "8") (pinfunction "GPB7_8") (pintype "bidirectional"))
      (node (ref "OK4") (pin "7") (pinfunction "EMIT_7") (pintype "passive"))
      (node (ref "R56") (pin "1") (pinfunction "1_1") (pintype "passive"))
    )
    (net (code "32") (name "/X6.1") (class "Default")
      (node (ref "IC5") (pin "5") (pinfunction "GPB4_5") (pintype "bidirectional"))
      (node (ref "OK8") (pin "5") (pinfunction "EMIT_5") (pintype "passive"))
      (node (ref "R63") (pin "1") (pinfunction "1_1") (pintype "passive"))
    )
    (net (code "33") (name "/X6.2") (class "Default")
      (node (ref "IC5") (pin "6") (pinfunction "GPB5_6") (pintype "bidirectional"))
      (node (ref "OK8") (pin "7") (pinfunction "EMIT_7") (pintype "passive"))
      (node (ref "R64") (pin "1") (pinfunction "1_1") (pintype "passive"))
    )
    (net (code "34") (name "/X7.1") (class "Default")
      (node (ref "IC5") (pin "3") (pinfunction "GPB2_3") (pintype "bidirectional"))
      (node (ref "OK2") (pin "5") (pinfunction "EMIT_5") (pintype "passive"))
      (node (ref "R51") (pin "1") (pinfunction "1_1") (pintype "passive"))
    )
    (net (code "35") (name "/X7.2") (class "Default")
      (node (ref "IC5") (pin "4") (pinfunction "GPB3_4") (pintype "bidirectional"))
      (node (ref "OK2") (pin "7") (pinfunction "EMIT_7") (pintype "passive"))
      (node (ref "R52") (pin "1") (pinfunction "1_1") (pintype "passive"))
    )
    (net (code "36") (name "/X8.1") (class "Default")
      (node (ref "IC5") (pin "1") (pinfunction "GPB0_1") (pintype "bidirectional"))
      (node (ref "OK5") (pin "5") (pinfunction "EMIT_5") (pintype "passive"))
      (node (ref "R57") (pin "1") (pinfunction "1_1") (pintype "passive"))
    )
    (net (code "37") (name "/X8.2") (class "Default")
      (node (ref "IC5") (pin "2") (pinfunction "GPB1_2") (pintype "bidirectional"))
      (node (ref "OK5") (pin "7") (pinfunction "EMIT_7") (pintype "passive"))
      (node (ref "R58") (pin "1") (pinfunction "1_1") (pintype "passive"))
    )
    (net (code "38") (name "/Z3V3") (class "Default")
      (node (ref "C19") (pin "1") (pinfunction "1_1") (pintype "passive"))
      (node (ref "C6") (pin "2") (pinfunction "2_2") (pintype "passive"))
      (node (ref "C7") (pin "2") (pinfunction "2_2") (pintype "passive"))
      (node (ref "IC2") (pin "8") (pinfunction "VCC_8") (pintype "power_in"))
      (node (ref "IC5") (pin "9") (pinfunction "VDD_9") (pintype "bidirectional"))
      (node (ref "IC7") (pin "1") (pinfunction "VCC_1") (pintype "power_in"))
      (node (ref "OK1") (pin "6") (pinfunction "COL_6") (pintype "passive"))
      (node (ref "OK1") (pin "8") (pinfunction "COL_8") (pintype "passive"))
      (node (ref "OK2") (pin "6") (pinfunction "COL_6") (pintype "passive"))
      (node (ref "OK2") (pin "8") (pinfunction "COL_8") (pintype "passive"))
      (node (ref "OK3") (pin "6") (pinfunction "COL_6") (pintype "passive"))
      (node (ref "OK3") (pin "8") (pinfunction "COL_8") (pintype "passive"))
      (node (ref "OK4") (pin "6") (pinfunction "COL_6") (pintype "passive"))
      (node (ref "OK4") (pin "8") (pinfunction "COL_8") (pintype "passive"))
      (node (ref "OK5") (pin "6") (pinfunction "COL_6") (pintype "passive"))
      (node (ref "OK5") (pin "8") (pinfunction "COL_8") (pintype "passive"))
      (node (ref "OK6") (pin "6") (pinfunction "COL_6") (pintype "passive"))
      (node (ref "OK6") (pin "8") (pinfunction "COL_8") (pintype "passive"))
      (node (ref "OK7") (pin "6") (pinfunction "COL_6") (pintype "passive"))
      (node (ref "OK7") (pin "8") (pinfunction "COL_8") (pintype "passive"))
      (node (ref "OK8") (pin "6") (pinfunction "COL_6") (pintype "passive"))
      (node (ref "OK8") (pin "8") (pinfunction "COL_8") (pintype "passive"))
      (node (ref "OK9") (pin "8") (pinfunction "COL_8") (pintype "passive"))
      (node (ref "R3") (pin "1") (pinfunction "1_1") (pintype "passive"))
      (node (ref "R34") (pin "2") (pinfunction "2_2") (pintype "passive"))
      (node (ref "R4") (pin "1") (pinfunction "1_1") (pintype "passive"))
      (node (ref "R6") (pin "2") (pinfunction "2_2") (pintype "passive"))
      (node (ref "R69") (pin "1") (pinfunction "1_1") (pintype "passive"))
      (node (ref "R7") (pin "2") (pinfunction "2_2") (pintype "passive"))
      (node (ref "R72") (pin "1") (pinfunction "1_1") (pintype "passive"))
      (node (ref "X0") (pin "1") (pinfunction "3V3_1") (pintype "power_in"))
      (node (ref "X0") (pin "17") (pinfunction "3V3_17") (pintype "power_in"))
    )
    (net (code "39") (name "GND") (class "Default")
      (node (ref "A0") (pin "3") (pinfunction "P$3_3") (pintype "power_in"))
      (node (ref "A1") (pin "3") (pinfunction "P$3_3") (pintype "power_in"))
      (node (ref "A2") (pin "3") (pinfunction "P$3_3") (pintype "power_in"))
      (node (ref "C1") (pin "1") (pinfunction "1_1") (pintype "passive"))
      (node (ref "C10") (pin "1") (pinfunction "1_1") (pintype "passive"))
      (node (ref "C11") (pin "-") (pinfunction "-_-") (pintype "passive"))
      (node (ref "C12") (pin "-") (pinfunction "-_-") (pintype "passive"))
      (node (ref "C13") (pin "1") (pinfunction "1_1") (pintype "passive"))
      (node (ref "C14") (pin "-") (pinfunction "-_-") (pintype "passive"))
      (node (ref "C15") (pin "1") (pinfunction "1_1") (pintype "passive"))
      (node (ref "C17") (pin "1") (pinfunction "1_1") (pintype "passive"))
      (node (ref "C19") (pin "2") (pinfunction "2_2") (pintype "passive"))
      (node (ref "C2") (pin "2") (pinfunction "2_2") (pintype "passive"))
      (node (ref "C22") (pin "1") (pinfunction "1_1") (pintype "passive"))
      (node (ref "C23") (pin "-") (pinfunction "-_-") (pintype "passive"))
      (node (ref "C3") (pin "2") (pinfunction "2_2") (pintype "passive"))
      (node (ref "C6") (pin "1") (pinfunction "1_1") (pintype "passive"))
      (node (ref "C7") (pin "1") (pinfunction "1_1") (pintype "passive"))
      (node (ref "C9") (pin "1") (pinfunction "1_1") (pintype "passive"))
      (node (ref "I2C") (pin "3") (pinfunction "3_3") (pintype "passive"))
      (node (ref "IC2") (pin "2") (pinfunction "RE/_2") (pintype "input"))
      (node (ref "IC2") (pin "5") (pinfunction "GND_5") (pintype "power_in"))
      (node (ref "IC4") (pin "2") (pinfunction "GND_2") (pintype "passive"))
      (node (ref "IC4") (pin "2@1") (pinfunction "GND_2@1") (pintype "passive"))
      (node (ref "IC5") (pin "10") (pinfunction "VSS_10") (pintype "bidirectional"))
      (node (ref "IC6") (pin "1") (pinfunction "GND_1") (pintype "power_in"))
      (node (ref "IC7") (pin "2") (pinfunction "GND_2") (pintype "power_in"))
      (node (ref "Q1") (pin "2") (pinfunction "S_2") (pintype "passive"))
      (node (ref "Q2") (pin "2") (pinfunction "S_2") (pintype "passive"))
      (node (ref "R10") (pin "1") (pinfunction "1_1") (pintype "passive"))
      (node (ref "R13") (pin "2") (pinfunction "2_2") (pintype "passive"))
      (node (ref "R29") (pin "1") (pinfunction "1_1") (pintype "passive"))
      (node (ref "R33") (pin "2") (pinfunction "2_2") (pintype "passive"))
      (node (ref "R35") (pin "1") (pinfunction "1_1") (pintype "passive"))
      (node (ref "R40") (pin "1") (pinfunction "1_1") (pintype "passive"))
      (node (ref "R49") (pin "2") (pinfunction "2_2") (pintype "passive"))
      (node (ref "R50") (pin "2") (pinfunction "2_2") (pintype "passive"))
      (node (ref "R51") (pin "2") (pinfunction "2_2") (pintype "passive"))
      (node (ref "R52") (pin "2") (pinfunction "2_2") (pintype "passive"))
      (node (ref "R53") (pin "2") (pinfunction "2_2") (pintype "passive"))
      (node (ref "R54") (pin "2") (pinfunction "2_2") (pintype "passive"))
      (node (ref "R55") (pin "2") (pinfunction "2_2") (pintype "passive"))
      (node (ref "R56") (pin "2") (pinfunction "2_2") (pintype "passive"))
      (node (ref "R57") (pin "2") (pinfunction "2_2") (pintype "passive"))
      (node (ref "R58") (pin "2") (pinfunction "2_2") (pintype "passive"))
      (node (ref "R59") (pin "2") (pinfunction "2_2") (pintype "passive"))
      (node (ref "R60") (pin "2") (pinfunction "2_2") (pintype "passive"))
      (node (ref "R61") (pin "2") (pinfunction "2_2") (pintype "passive"))
      (node (ref "R62") (pin "2") (pinfunction "2_2") (pintype "passive"))
      (node (ref "R63") (pin "2") (pinfunction "2_2") (pintype "passive"))
      (node (ref "R64") (pin "2") (pinfunction "2_2") (pintype "passive"))
      (node (ref "R66") (pin "2") (pinfunction "2_2") (pintype "passive"))
      (node (ref "R68") (pin "1") (pinfunction "1_1") (pintype "passive"))
      (node (ref "R70") (pin "2") (pinfunction "2_2") (pintype "passive"))
      (node (ref "SWD") (pin "4") (pinfunction "4_4") (pintype "passive"))
      (node (ref "TVS1") (pin "A") (pinfunction "A_A") (pintype "passive"))
      (node (ref "TVS2") (pin "A") (pinfunction "A_A") (pintype "passive"))
      (node (ref "U2") (pin "23") (pinfunction "VSS_1_23") (pintype "power_in"))
      (node (ref "U2") (pin "35") (pinfunction "VSS_2_35") (pintype "power_in"))
      (node (ref "U2") (pin "47") (pinfunction "VSS_3_47") (pintype "power_in"))
      (node (ref "U2") (pin "8") (pinfunction "VSSA_8") (pintype "power_in"))
      (node (ref "UART") (pin "3") (pinfunction "3_3") (pintype "passive"))
      (node (ref "X0") (pin "14") (pinfunction "GND_14") (pintype "power_in"))
      (node (ref "X0") (pin "20") (pinfunction "GND_20") (pintype "power_in"))
      (node (ref "X0") (pin "25") (pinfunction "GND_25") (pintype "power_in"))
      (node (ref "X0") (pin "6") (pinfunction "GND_6") (pintype "power_in"))
      (node (ref "X0") (pin "9") (pinfunction "GND_9") (pintype "power_in"))
      (node (ref "X10") (pin "1") (pinfunction "KL_1") (pintype "passive"))
      (node (ref "X9") (pin "3") (pinfunction "KL_3") (pintype "passive"))
    )
    (net (code "40") (name "Net-(A0-P$1)") (class "Default")
      (node (ref "A0") (pin "2") (pinfunction "P$1_2") (pintype "bidirectional"))
      (node (ref "IC5") (pin "15") (pinfunction "A0_15") (pintype "bidirectional"))
    )
    (net (code "41") (name "Net-(A0-P$2)") (class "Default")
      (node (ref "A0") (pin "1") (pinfunction "P$2_1") (pintype "power_in"))
      (node (ref "A1") (pin "1") (pinfunction "P$2_1") (pintype "power_in"))
      (node (ref "A2") (pin "1") (pinfunction "P$2_1") (pintype "power_in"))
      (node (ref "C17") (pin "2") (pinfunction "2_2") (pintype "passive"))
      (node (ref "C23") (pin "+") (pinfunction "+_+") (pintype "passive"))
      (node (ref "C3") (pin "1") (pinfunction "1_1") (pintype "passive"))
      (node (ref "FB1") (pin "1") (pinfunction "1_1") (pintype "passive"))
      (node (ref "IC4") (pin "1") (pinfunction "VO_1") (pintype "passive"))
      (node (ref "LED1") (pin "A") (pinfunction "A_A") (pintype "passive"))
      (node (ref "LED2") (pin "A") (pinfunction "A_A") (pintype "passive"))
      (node (ref "R14") (pin "2") (pinfunction "2_2") (pintype "passive"))
      (node (ref "R41") (pin "2") (pinfunction "2_2") (pintype "passive"))
      (node (ref "R8") (pin "2") (pinfunction "2_2") (pintype "passive"))
      (node (ref "SWD") (pin "1") (pinfunction "1_1") (pintype "passive"))
      (node (ref "U2") (pin "24") (pinfunction "VDD_1_24") (pintype "power_in"))
      (node (ref "U2") (pin "36") (pinfunction "VDD_2_36") (pintype "power_in"))
      (node (ref "U2") (pin "48") (pinfunction "VDD_3_48") (pintype "power_in"))
    )
    (net (code "42") (name "Net-(A1-P$1)") (class "Default")
      (node (ref "A1") (pin "2") (pinfunction "P$1_2") (pintype "bidirectional"))
      (node (ref "IC5") (pin "16") (pinfunction "A1_16") (pintype "bidirectional"))
    )
    (net (code "43") (name "Net-(A2-P$1)") (class "Default")
      (node (ref "A2") (pin "2") (pinfunction "P$1_2") (pintype "bidirectional"))
      (node (ref "IC5") (pin "17") (pinfunction "A2_17") (pintype "bidirectional"))
    )
    (net (code "44") (name "Net-(IC2-A)") (class "Default")
      (node (ref "IC2") (pin "6") (pinfunction "A_6") (pintype "passive"))
      (node (ref "R9") (pin "1") (pinfunction "1_1") (pintype "passive"))
      (node (ref "TVS1") (pin "C") (pinfunction "C_C") (pintype "passive"))
      (node (ref "X10") (pin "2") (pinfunction "KL_2") (pintype "passive"))
    )
    (net (code "45") (name "Net-(IC2-B)") (class "Default")
      (node (ref "IC2") (pin "7") (pinfunction "B_7") (pintype "passive"))
      (node (ref "R9") (pin "2") (pinfunction "2_2") (pintype "passive"))
      (node (ref "TVS2") (pin "C") (pinfunction "C_C") (pintype "passive"))
      (node (ref "X10") (pin "3") (pinfunction "KL_3") (pintype "passive"))
    )
    (net (code "46") (name "Net-(IC2-DE)") (class "Default")
      (node (ref "IC2") (pin "3") (pinfunction "DE_3") (pintype "input"))
      (node (ref "X0") (pin "22") (pinfunction "UART2_RTS/PA02_22") (pintype "bidirectional"))
    )
    (net (code "47") (name "Net-(IC2-DI)") (class "Default")
      (node (ref "IC2") (pin "4") (pinfunction "DI_4") (pintype "input"))
      (node (ref "X0") (pin "13") (pinfunction "UART2_TX/PA00_13") (pintype "bidirectional"))
    )
    (net (code "48") (name "Net-(IC2-RO)") (class "Default")
      (node (ref "IC2") (pin "1") (pinfunction "RO_1") (pintype "output"))
      (node (ref "X0") (pin "11") (pinfunction "UART2_RX/PA01_11") (pintype "bidirectional"))
    )
    (net (code "49") (name "Net-(IC3-VIN+)") (class "Default")
      (node (ref "C18") (pin "2") (pinfunction "2_2") (pintype "passive"))
      (node (ref "FB2") (pin "1") (pinfunction "1_1") (pintype "passive"))
      (node (ref "IC3") (pin "2") (pinfunction "VIN+_2") (pintype "bidirectional"))
    )
    (net (code "50") (name "Net-(IC3-VIN-)") (class "Default")
      (node (ref "C18") (pin "1") (pinfunction "1_1") (pintype "passive"))
      (node (ref "IC3") (pin "1") (pinfunction "VIN-_1") (pintype "bidirectional"))
      (node (ref "Q1") (pin "3") (pinfunction "D_3") (pintype "passive"))
    )
    (net (code "51") (name "Net-(IC3-VOUT+)") (class "Default")
      (node (ref "C16") (pin "1") (pinfunction "1_1") (pintype "passive"))
      (node (ref "IC3") (pin "4") (pinfunction "VOUT+_4") (pintype "bidirectional"))
      (node (ref "R17") (pin "2") (pinfunction "2_2") (pintype "passive"))
      (node (ref "R20") (pin "2") (pinfunction "2_2") (pintype "passive"))
      (node (ref "R25") (pin "2") (pinfunction "2_2") (pintype "passive"))
      (node (ref "R31") (pin "2") (pinfunction "2_2") (pintype "passive"))
      (node (ref "R37") (pin "2") (pinfunction "2_2") (pintype "passive"))
      (node (ref "R42") (pin "2") (pinfunction "2_2") (pintype "passive"))
      (node (ref "R45") (pin "2") (pinfunction "2_2") (pintype "passive"))
      (node (ref "R48") (pin "2") (pinfunction "2_2") (pintype "passive"))
      (node (ref "R65") (pin "1") (pinfunction "1_1") (pintype "passive"))
    )
    (net (code "52") (name "Net-(IC3-VOUT-)") (class "Default")
      (node (ref "C16") (pin "2") (pinfunction "2_2") (pintype "passive"))
      (node (ref "IC3") (pin "3") (pinfunction "VOUT-_3") (pintype "bidirectional"))
      (node (ref "OK1") (pin "2") (pinfunction "C_2") (pintype "passive"))
      (node (ref "OK1") (pin "4") (pinfunction "C_4") (pintype "passive"))
      (node (ref "OK2") (pin "2") (pinfunction "C_2") (pintype "passive"))
      (node (ref "OK2") (pin "4") (pinfunction "C_4") (pintype "passive"))
      (node (ref "OK3") (pin "2") (pinfunction "C_2") (pintype "passive"))
      (node (ref "OK3") (pin "4") (pinfunction "C_4") (pintype "passive"))
      (node (ref "OK4") (pin "2") (pinfunction "C_2") (pintype "passive"))
      (node (ref "OK4") (pin "4") (pinfunction "C_4") (pintype "passive"))
      (node (ref "OK5") (pin "2") (pinfunction "C_2") (pintype "passive"))
      (node (ref "OK5") (pin "4") (pinfunction "C_4") (pintype "passive"))
      (node (ref "OK6") (pin "2") (pinfunction "C_2") (pintype "passive"))
      (node (ref "OK6") (pin "4") (pinfunction "C_4") (pintype "passive"))
      (node (ref "OK7") (pin "2") (pinfunction "C_2") (pintype "passive"))
      (node (ref "OK7") (pin "4") (pinfunction "C_4") (pintype "passive"))
      (node (ref "OK8") (pin "2") (pinfunction "C_2") (pintype "passive"))
      (node (ref "OK8") (pin "4") (pinfunction "C_4") (pintype "passive"))
      (node (ref "OK9") (pin "2") (pinfunction "C_2") (pintype "passive"))
      (node (ref "TVS10") (pin "A") (pinfunction "A_A") (pintype "passive"))
      (node (ref "TVS11") (pin "A") (pinfunction "A_A") (pintype "passive"))
      (node (ref "TVS12") (pin "A") (pinfunction "A_A") (pintype "passive"))
      (node (ref "TVS13") (pin "A") (pinfunction "A_A") (pintype "passive"))
      (node (ref "TVS14") (pin "A") (pinfunction "A_A") (pintype "passive"))
      (node (ref "TVS15") (pin "A") (pinfunction "A_A") (pintype "passive"))
      (node (ref "TVS16") (pin "A") (pinfunction "A_A") (pintype "passive"))
      (node (ref "TVS17") (pin "A") (pinfunction "A_A") (pintype "passive"))
      (node (ref "TVS18") (pin "A") (pinfunction "A_A") (pintype "passive"))
      (node (ref "TVS3") (pin "A") (pinfunction "A_A") (pintype "passive"))
      (node (ref "TVS4") (pin "A") (pinfunction "A_A") (pintype "passive"))
      (node (ref "TVS5") (pin "A") (pinfunction "A_A") (pintype "passive"))
      (node (ref "TVS6") (pin "A") (pinfunction "A_A") (pintype "passive"))
      (node (ref "TVS7") (pin "A") (pinfunction "A_A") (pintype "passive"))
      (node (ref "TVS8") (pin "A") (pinfunction "A_A") (pintype "passive"))
      (node (ref "TVS9") (pin "A") (pinfunction "A_A") (pintype "passive"))
    )
    (net (code "53") (name "Net-(IC5-INTA)") (class "Default")
      (node (ref "IC5") (pin "19") (pinfunction "INTA_19") (pintype "bidirectional"))
      (node (ref "X0") (pin "26") (pinfunction "SIM_DET/PA_EINT10/PA10_26") (pintype "bidirectional"))
    )
    (net (code "54") (name "Net-(IC6-BST)") (class "Default")
      (node (ref "C8") (pin "1") (pinfunction "1_1") (pintype "passive"))
      (node (ref "IC6") (pin "6") (pinfunction "BST_6") (pintype "input"))
    )
    (net (code "55") (name "Net-(IC6-FB)") (class "Default")
      (node (ref "IC6") (pin "4") (pinfunction "FB_4") (pintype "input"))
      (node (ref "R10") (pin "2") (pinfunction "2_2") (pintype "passive"))
      (node (ref "R11") (pin "2") (pinfunction "2_2") (pintype "passive"))
    )
    (net (code "56") (name "Net-(IC6-SW)") (class "Default")
      (node (ref "C8") (pin "2") (pinfunction "2_2") (pintype "passive"))
      (node (ref "IC6") (pin "2") (pinfunction "SW_2") (pintype "passive"))
      (node (ref "L4.7") (pin "P$1") (pinfunction "1_P$1") (pintype "passive"))
    )
    (net (code "57") (name "Net-(L4.7-2)") (class "Default")
      (node (ref "C14") (pin "+") (pinfunction "+_+") (pintype "passive"))
      (node (ref "C22") (pin "2") (pinfunction "2_2") (pintype "passive"))
      (node (ref "C9") (pin "2") (pinfunction "2_2") (pintype "passive"))
      (node (ref "L4.7") (pin "P$2") (pinfunction "2_P$2") (pintype "passive"))
      (node (ref "R11") (pin "1") (pinfunction "1_1") (pintype "passive"))
      (node (ref "R5") (pin "2") (pinfunction "2_2") (pintype "passive"))
      (node (ref "X0") (pin "2") (pinfunction "5V_2") (pintype "power_in"))
      (node (ref "X0") (pin "4") (pinfunction "5V_4") (pintype "power_in"))
    )
    (net (code "58") (name "Net-(LED1-PadC)") (class "Default")
      (node (ref "LED1") (pin "C") (pinfunction "C_C") (pintype "passive"))
      (node (ref "R22") (pin "1") (pinfunction "1_1") (pintype "passive"))
    )
    (net (code "59") (name "Net-(LED2-PadC)") (class "Default")
      (node (ref "LED2") (pin "C") (pinfunction "C_C") (pintype "passive"))
      (node (ref "R23") (pin "1") (pinfunction "1_1") (pintype "passive"))
    )
    (net (code "60") (name "Net-(OK1A-A)") (class "Default")
      (node (ref "OK1") (pin "1") (pinfunction "A_1") (pintype "passive"))
      (node (ref "R16") (pin "2") (pinfunction "2_2") (pintype "passive"))
    )
    (net (code "61") (name "Net-(OK1B-A)") (class "Default")
      (node (ref "OK1") (pin "3") (pinfunction "A_3") (pintype "passive"))
      (node (ref "R15") (pin "2") (pinfunction "2_2") (pintype "passive"))
    )
    (net (code "62") (name "Net-(OK2A-A)") (class "Default")
      (node (ref "OK2") (pin "1") (pinfunction "A_1") (pintype "passive"))
      (node (ref "R19") (pin "2") (pinfunction "2_2") (pintype "passive"))
    )
    (net (code "63") (name "Net-(OK2B-A)") (class "Default")
      (node (ref "OK2") (pin "3") (pinfunction "A_3") (pintype "passive"))
      (node (ref "R18") (pin "2") (pinfunction "2_2") (pintype "passive"))
    )
    (net (code "64") (name "Net-(OK3A-A)") (class "Default")
      (node (ref "OK3") (pin "1") (pinfunction "A_1") (pintype "passive"))
      (node (ref "R24") (pin "2") (pinfunction "2_2") (pintype "passive"))
    )
    (net (code "65") (name "Net-(OK3B-A)") (class "Default")
      (node (ref "OK3") (pin "3") (pinfunction "A_3") (pintype "passive"))
      (node (ref "R21") (pin "2") (pinfunction "2_2") (pintype "passive"))
    )
    (net (code "66") (name "Net-(OK4A-A)") (class "Default")
      (node (ref "OK4") (pin "1") (pinfunction "A_1") (pintype "passive"))
      (node (ref "R27") (pin "2") (pinfunction "2_2") (pintype "passive"))
    )
    (net (code "67") (name "Net-(OK4B-A)") (class "Default")
      (node (ref "OK4") (pin "3") (pinfunction "A_3") (pintype "passive"))
      (node (ref "R26") (pin "2") (pinfunction "2_2") (pintype "passive"))
    )
    (net (code "68") (name "Net-(OK5A-A)") (class "Default")
      (node (ref "OK5") (pin "1") (pinfunction "A_1") (pintype "passive"))
      (node (ref "R36") (pin "2") (pinfunction "2_2") (pintype "passive"))
    )
    (net (code "69") (name "Net-(OK5B-A)") (class "Default")
      (node (ref "OK5") (pin "3") (pinfunction "A_3") (pintype "passive"))
      (node (ref "R32") (pin "2") (pinfunction "2_2") (pintype "passive"))
    )
    (net (code "70") (name "Net-(OK6A-A)") (class "Default")
      (node (ref "OK6") (pin "1") (pinfunction "A_1") (pintype "passive"))
      (node (ref "R39") (pin "2") (pinfunction "2_2") (pintype "passive"))
    )
    (net (code "71") (name "Net-(OK6B-A)") (class "Default")
      (node (ref "OK6") (pin "3") (pinfunction "A_3") (pintype "passive"))
      (node (ref "R38") (pin "2") (pinfunction "2_2") (pintype "passive"))
    )
    (net (code "72") (name "Net-(OK7A-A)") (class "Default")
      (node (ref "OK7") (pin "1") (pinfunction "A_1") (pintype "passive"))
      (node (ref "R44") (pin "2") (pinfunction "2_2") (pintype "passive"))
    )
    (net (code "73") (name "Net-(OK7B-A)") (class "Default")
      (node (ref "OK7") (pin "3") (pinfunction "A_3") (pintype "passive"))
      (node (ref "R43") (pin "2") (pinfunction "2_2") (pintype "passive"))
    )
    (net (code "74") (name "Net-(OK8A-A)") (class "Default")
      (node (ref "OK8") (pin "1") (pinfunction "A_1") (pintype "passive"))
      (node (ref "R47") (pin "2") (pinfunction "2_2") (pintype "passive"))
    )
    (net (code "75") (name "Net-(OK8B-A)") (class "Default")
      (node (ref "OK8") (pin "3") (pinfunction "A_3") (pintype "passive"))
      (node (ref "R46") (pin "2") (pinfunction "2_2") (pintype "passive"))
    )
    (net (code "76") (name "Net-(OK9A-A)") (class "Default")
      (node (ref "OK9") (pin "1") (pinfunction "A_1") (pintype "passive"))
      (node (ref "R65") (pin "2") (pinfunction "2_2") (pintype "passive"))
    )
    (net (code "77") (name "Net-(Q1-G)") (class "Default")
      (node (ref "Q1") (pin "1") (pinfunction "G_1") (pintype "passive"))
      (node (ref "R67") (pin "1") (pinfunction "1_1") (pintype "passive"))
    )
    (net (code "78") (name "Net-(Q2-D)") (class "Default")
      (node (ref "Q2") (pin "3") (pinfunction "D_3") (pintype "passive"))
      (node (ref "R28") (pin "1") (pinfunction "1_1") (pintype "passive"))
    )
    (net (code "79") (name "Net-(Q2-G)") (class "Default")
      (node (ref "Q2") (pin "1") (pinfunction "G_1") (pintype "passive"))
      (node (ref "R71") (pin "2") (pinfunction "2_2") (pintype "passive"))
    )
    (net (code "80") (name "Net-(U2-VBAT)") (class "Default")
      (node (ref "C2") (pin "1") (pinfunction "1_1") (pintype "passive"))
      (node (ref "FB1") (pin "2") (pinfunction "2_2") (pintype "passive"))
      (node (ref "U2") (pin "1") (pinfunction "VBAT_1") (pintype "power_in"))
      (node (ref "U2") (pin "9") (pinfunction "VDDA_9") (pintype "power_in"))
    )
    (net (code "81") (name "Net-(X0-PWM1{slash}PA06)") (class "Default")
      (node (ref "R70") (pin "1") (pinfunction "1_1") (pintype "passive"))
      (node (ref "R71") (pin "1") (pinfunction "1_1") (pintype "passive"))
      (node (ref "X0") (pin "7") (pinfunction "PWM1/PA06_7") (pintype "bidirectional"))
    )
    (net (code "82") (name "Net-(X0-UART1_RX{slash}PG07)") (class "Default")
      (node (ref "R1") (pin "2") (pinfunction "2_2") (pintype "passive"))
      (node (ref "R3") (pin "2") (pinfunction "2_2") (pintype "passive"))
      (node (ref "UART") (pin "2") (pinfunction "2_2") (pintype "passive"))
      (node (ref "X0") (pin "10") (pinfunction "UART1_RX/PG07_10") (pintype "bidirectional"))
    )
    (net (code "83") (name "Net-(X0-UART1_TX{slash}PG06)") (class "Default")
      (node (ref "R2") (pin "2") (pinfunction "2_2") (pintype "passive"))
      (node (ref "R4") (pin "2") (pinfunction "2_2") (pintype "passive"))
      (node (ref "UART") (pin "1") (pinfunction "1_1") (pintype "passive"))
      (node (ref "X0") (pin "8") (pinfunction "UART1_TX/PG06_8") (pintype "bidirectional"))
    )
    (net (code "84") (name "Net-(X1A-KL)") (class "Default")
      (node (ref "R21") (pin "1") (pinfunction "1_1") (pintype "passive"))
      (node (ref "TVS7") (pin "C") (pinfunction "C_C") (pintype "passive"))
      (node (ref "X1") (pin "1") (pinfunction "KL_1") (pintype "passive"))
    )
    (net (code "85") (name "Net-(X1B-KL)") (class "Default")
      (node (ref "R24") (pin "1") (pinfunction "1_1") (pintype "passive"))
      (node (ref "TVS8") (pin "C") (pinfunction "C_C") (pintype "passive"))
      (node (ref "X1") (pin "2") (pinfunction "KL_2") (pintype "passive"))
    )
    (net (code "86") (name "Net-(X1C-KL)") (class "Default")
      (node (ref "R25") (pin "1") (pinfunction "1_1") (pintype "passive"))
      (node (ref "X1") (pin "3") (pinfunction "KL_3") (pintype "passive"))
    )
    (net (code "87") (name "Net-(X2A-KL)") (class "Default")
      (node (ref "R43") (pin "1") (pinfunction "1_1") (pintype "passive"))
      (node (ref "TVS15") (pin "C") (pinfunction "C_C") (pintype "passive"))
      (node (ref "X2") (pin "1") (pinfunction "KL_1") (pintype "passive"))
    )
    (net (code "88") (name "Net-(X2B-KL)") (class "Default")
      (node (ref "R44") (pin "1") (pinfunction "1_1") (pintype "passive"))
      (node (ref "TVS16") (pin "C") (pinfunction "C_C") (pintype "passive"))
      (node (ref "X2") (pin "2") (pinfunction "KL_2") (pintype "passive"))
    )
    (net (code "89") (name "Net-(X2C-KL)") (class "Default")
      (node (ref "R45") (pin "1") (pinfunction "1_1") (pintype "passive"))
      (node (ref "X2") (pin "3") (pinfunction "KL_3") (pintype "passive"))
    )
    (net (code "90") (name "Net-(X3A-KL)") (class "Default")
      (node (ref "R38") (pin "1") (pinfunction "1_1") (pintype "passive"))
      (node (ref "TVS13") (pin "C") (pinfunction "C_C") (pintype "passive"))
      (node (ref "X3") (pin "1") (pinfunction "KL_1") (pintype "passive"))
    )
    (net (code "91") (name "Net-(X3B-KL)") (class "Default")
      (node (ref "R39") (pin "1") (pinfunction "1_1") (pintype "passive"))
      (node (ref "TVS14") (pin "C") (pinfunction "C_C") (pintype "passive"))
      (node (ref "X3") (pin "2") (pinfunction "KL_2") (pintype "passive"))
    )
    (net (code "92") (name "Net-(X3C-KL)") (class "Default")
      (node (ref "R42") (pin "1") (pinfunction "1_1") (pintype "passive"))
      (node (ref "X3") (pin "3") (pinfunction "KL_3") (pintype "passive"))
    )
    (net (code "93") (name "Net-(X4A-KL)") (class "Default")
      (node (ref "R15") (pin "1") (pinfunction "1_1") (pintype "passive"))
      (node (ref "TVS3") (pin "C") (pinfunction "C_C") (pintype "passive"))
      (node (ref "X4") (pin "1") (pinfunction "KL_1") (pintype "passive"))
    )
    (net (code "94") (name "Net-(X4B-KL)") (class "Default")
      (node (ref "R16") (pin "1") (pinfunction "1_1") (pintype "passive"))
      (node (ref "TVS4") (pin "C") (pinfunction "C_C") (pintype "passive"))
      (node (ref "X4") (pin "2") (pinfunction "KL_2") (pintype "passive"))
    )
    (net (code "95") (name "Net-(X4C-KL)") (class "Default")
      (node (ref "R17") (pin "1") (pinfunction "1_1") (pintype "passive"))
      (node (ref "X4") (pin "3") (pinfunction "KL_3") (pintype "passive"))
    )
    (net (code "96") (name "Net-(X5A-KL)") (class "Default")
      (node (ref "R26") (pin "1") (pinfunction "1_1") (pintype "passive"))
      (node (ref "TVS9") (pin "C") (pinfunction "C_C") (pintype "passive"))
      (node (ref "X5") (pin "1") (pinfunction "KL_1") (pintype "passive"))
    )
    (net (code "97") (name "Net-(X5B-KL)") (class "Default")
      (node (ref "R27") (pin "1") (pinfunction "1_1") (pintype "passive"))
      (node (ref "TVS10") (pin "C") (pinfunction "C_C") (pintype "passive"))
      (node (ref "X5") (pin "2") (pinfunction "KL_2") (pintype "passive"))
    )
    (net (code "98") (name "Net-(X5C-KL)") (class "Default")
      (node (ref "R31") (pin "1") (pinfunction "1_1") (pintype "passive"))
      (node (ref "X5") (pin "3") (pinfunction "KL_3") (pintype "passive"))
    )
    (net (code "99") (name "Net-(X6A-KL)") (class "Default")
      (node (ref "R46") (pin "1") (pinfunction "1_1") (pintype "passive"))
      (node (ref "TVS17") (pin "C") (pinfunction "C_C") (pintype "passive"))
      (node (ref "X6") (pin "1") (pinfunction "KL_1") (pintype "passive"))
    )
    (net (code "100") (name "Net-(X6B-KL)") (class "Default")
      (node (ref "R47") (pin "1") (pinfunction "1_1") (pintype "passive"))
      (node (ref "TVS18") (pin "C") (pinfunction "C_C") (pintype "passive"))
      (node (ref "X6") (pin "2") (pinfunction "KL_2") (pintype "passive"))
    )
    (net (code "101") (name "Net-(X6C-KL)") (class "Default")
      (node (ref "R48") (pin "1") (pinfunction "1_1") (pintype "passive"))
      (node (ref "X6") (pin "3") (pinfunction "KL_3") (pintype "passive"))
    )
    (net (code "102") (name "Net-(X7A-KL)") (class "Default")
      (node (ref "R18") (pin "1") (pinfunction "1_1") (pintype "passive"))
      (node (ref "TVS5") (pin "C") (pinfunction "C_C") (pintype "passive"))
      (node (ref "X7") (pin "1") (pinfunction "KL_1") (pintype "passive"))
    )
    (net (code "103") (name "Net-(X7B-KL)") (class "Default")
      (node (ref "R19") (pin "1") (pinfunction "1_1") (pintype "passive"))
      (node (ref "TVS6") (pin "C") (pinfunction "C_C") (pintype "passive"))
      (node (ref "X7") (pin "2") (pinfunction "KL_2") (pintype "passive"))
    )
    (net (code "104") (name "Net-(X7C-KL)") (class "Default")
      (node (ref "R20") (pin "1") (pinfunction "1_1") (pintype "passive"))
      (node (ref "X7") (pin "3") (pinfunction "KL_3") (pintype "passive"))
    )
    (net (code "105") (name "Net-(X8A-KL)") (class "Default")
      (node (ref "R32") (pin "1") (pinfunction "1_1") (pintype "passive"))
      (node (ref "TVS11") (pin "C") (pinfunction "C_C") (pintype "passive"))
      (node (ref "X8") (pin "1") (pinfunction "KL_1") (pintype "passive"))
    )
    (net (code "106") (name "Net-(X8B-KL)") (class "Default")
      (node (ref "R36") (pin "1") (pinfunction "1_1") (pintype "passive"))
      (node (ref "TVS12") (pin "C") (pinfunction "C_C") (pintype "passive"))
      (node (ref "X8") (pin "2") (pinfunction "KL_2") (pintype "passive"))
    )
    (net (code "107") (name "Net-(X8C-KL)") (class "Default")
      (node (ref "R37") (pin "1") (pinfunction "1_1") (pintype "passive"))
      (node (ref "X8") (pin "3") (pinfunction "KL_3") (pintype "passive"))
    )
    (net (code "108") (name "Net-(X9A-KL)") (class "Default")
      (node (ref "D10") (pin "A") (pinfunction "A_A") (pintype "passive"))
      (node (ref "R30") (pin "1") (pinfunction "1_1") (pintype "passive"))
      (node (ref "X9") (pin "1") (pinfunction "KL_1") (pintype "passive"))
    )
    (net (code "109") (name "Net-(X9B-KL)") (class "Default")
      (node (ref "D5") (pin "A") (pinfunction "A_A") (pintype "passive"))
      (node (ref "X9") (pin "2") (pinfunction "KL_2") (pintype "passive"))
    )
    (net (code "110") (name "Net-(X10D-KL)") (class "Default")
      (node (ref "C15") (pin "2") (pinfunction "2_2") (pintype "passive"))
      (node (ref "FS1") (pin "1") (pinfunction "1_1") (pintype "passive"))
      (node (ref "X10") (pin "4") (pinfunction "KL_4") (pintype "passive"))
    )
    (net (code "111") (name "unconnected-(IC5-NC-Pad11)") (class "Default")
      (node (ref "IC5") (pin "11") (pinfunction "NC_11") (pintype "bidirectional"))
    )
    (net (code "112") (name "unconnected-(IC5-NC-Pad14)") (class "Default")
      (node (ref "IC5") (pin "14") (pinfunction "NC_14") (pintype "bidirectional"))
    )
    (net (code "113") (name "unconnected-(IC7-NC-Pad3)") (class "Default")
      (node (ref "IC7") (pin "3") (pinfunction "NC_3") (pintype "no_connect"))
    )
    (net (code "114") (name "unconnected-(OK9B-A-Pad3)") (class "Default")
      (node (ref "OK9") (pin "3") (pinfunction "A_3") (pintype "passive"))
    )
    (net (code "115") (name "unconnected-(OK9B-C-Pad4)") (class "Default")
      (node (ref "OK9") (pin "4") (pinfunction "C_4") (pintype "passive"))
    )
    (net (code "116") (name "unconnected-(OK9B-COL-Pad6)") (class "Default")
      (node (ref "OK9") (pin "6") (pinfunction "COL_6") (pintype "passive"))
    )
    (net (code "117") (name "unconnected-(OK9B-EMIT-Pad5)") (class "Default")
      (node (ref "OK9") (pin "5") (pinfunction "EMIT_5") (pintype "passive"))
    )
    (net (code "118") (name "unconnected-(U2-BOOT0-Pad44)") (class "Default")
      (node (ref "U2") (pin "44") (pinfunction "BOOT0_44") (pintype "input"))
    )
    (net (code "119") (name "unconnected-(U2-PA4-Pad14)") (class "Default")
      (node (ref "U2") (pin "14") (pinfunction "PA4_14") (pintype "bidirectional"))
    )
    (net (code "120") (name "unconnected-(U2-PA5-Pad15)") (class "Default")
      (node (ref "U2") (pin "15") (pinfunction "PA5_15") (pintype "bidirectional"))
    )
    (net (code "121") (name "unconnected-(U2-PA6-Pad16)") (class "Default")
      (node (ref "U2") (pin "16") (pinfunction "PA6_16") (pintype "bidirectional"))
    )
    (net (code "122") (name "unconnected-(U2-PA7-Pad17)") (class "Default")
      (node (ref "U2") (pin "17") (pinfunction "PA7_17") (pintype "bidirectional"))
    )
    (net (code "123") (name "unconnected-(U2-PA8-Pad29)") (class "Default")
      (node (ref "U2") (pin "29") (pinfunction "PA8_29") (pintype "bidirectional"))
    )
    (net (code "124") (name "unconnected-(U2-PA11-Pad32)") (class "Default")
      (node (ref "U2") (pin "32") (pinfunction "PA11_32") (pintype "bidirectional"))
    )
    (net (code "125") (name "unconnected-(U2-PA12-Pad33)") (class "Default")
      (node (ref "U2") (pin "33") (pinfunction "PA12_33") (pintype "bidirectional"))
    )
    (net (code "126") (name "unconnected-(U2-PB0-Pad18)") (class "Default")
      (node (ref "U2") (pin "18") (pinfunction "PB0_18") (pintype "bidirectional"))
    )
    (net (code "127") (name "unconnected-(U2-PB2-Pad20)") (class "Default")
      (node (ref "U2") (pin "20") (pinfunction "PB2_20") (pintype "bidirectional"))
    )
    (net (code "128") (name "unconnected-(U2-PB10-Pad21)") (class "Default")
      (node (ref "U2") (pin "21") (pinfunction "PB10_21") (pintype "bidirectional"))
    )
    (net (code "129") (name "unconnected-(U2-PB11-Pad22)") (class "Default")
      (node (ref "U2") (pin "22") (pinfunction "PB11_22") (pintype "bidirectional"))
    )
    (net (code "130") (name "unconnected-(U2-PB12-Pad25)") (class "Default")
      (node (ref "U2") (pin "25") (pinfunction "PB12_25") (pintype "bidirectional"))
    )
    (net (code "131") (name "unconnected-(U2-PB14-Pad27)") (class "Default")
      (node (ref "U2") (pin "27") (pinfunction "PB14_27") (pintype "bidirectional"))
    )
    (net (code "132") (name "unconnected-(U2-PC13-TAMPER-RTC-Pad2)") (class "Default")
      (node (ref "U2") (pin "2") (pinfunction "PC13-TAMPER-RTC_2") (pintype "bidirectional"))
    )
    (net (code "133") (name "unconnected-(U2-PC14-OSC32_IN-Pad3)") (class "Default")
      (node (ref "U2") (pin "3") (pinfunction "PC14-OSC32_IN_3") (pintype "bidirectional"))
    )
    (net (code "134") (name "unconnected-(U2-PC15-OSC32_OUT-Pad4)") (class "Default")
      (node (ref "U2") (pin "4") (pinfunction "PC15-OSC32_OUT_4") (pintype "bidirectional"))
    )
    (net (code "135") (name "unconnected-(U2-PD0-OSC_IN-Pad5)") (class "Default")
      (node (ref "U2") (pin "5") (pinfunction "PD0-OSC_IN_5") (pintype "input"))
    )
    (net (code "136") (name "unconnected-(U2-PD1-OSC_OUT-Pad6)") (class "Default")
      (node (ref "U2") (pin "6") (pinfunction "PD1-OSC_OUT_6") (pintype "output"))
    )
    (net (code "137") (name "unconnected-(X0-PA13{slash}SPI1_CS-Pad24)") (class "Default")
      (node (ref "X0") (pin "24") (pinfunction "PA13/SPI1_CS_24") (pintype "bidirectional"))
    )
    (net (code "138") (name "unconnected-(X0-PA14{slash}SPI1_CLK-Pad23)") (class "Default")
      (node (ref "X0") (pin "23") (pinfunction "PA14/SPI1_CLK_23") (pintype "bidirectional"))
    )
    (net (code "139") (name "unconnected-(X0-PA15{slash}SPI1_MOSI-Pad19)") (class "Default")
      (node (ref "X0") (pin "19") (pinfunction "PA15/SPI1_MOSI_19") (pintype "bidirectional"))
    )
    (net (code "140") (name "unconnected-(X0-PA16{slash}SPI1_MISO-Pad21)") (class "Default")
      (node (ref "X0") (pin "21") (pinfunction "PA16/SPI1_MISO_21") (pintype "bidirectional"))
    )
    (net (code "141") (name "unconnected-(X0-PA18{slash}TWI1_SCL-Pad18)") (class "Default")
      (node (ref "X0") (pin "18") (pinfunction "PA18/TWI1_SCL_18") (pintype "bidirectional"))
    )
    (net (code "142") (name "unconnected-(X0-PA19{slash}TWI1_SDA-Pad16)") (class "Default")
      (node (ref "X0") (pin "16") (pinfunction "PA19/TWI1_SDA_16") (pintype "bidirectional"))
    )
    (net (code "143") (name "unconnected-(X0-UART2_CTS{slash}PA03-Pad15)") (class "Default")
      (node (ref "X0") (pin "15") (pinfunction "UART2_CTS/PA03_15") (pintype "bidirectional"))
    )
  )
)
